# Ver_5_MAIN.net
KiCad netlist of a schematic drawn in EAGLE
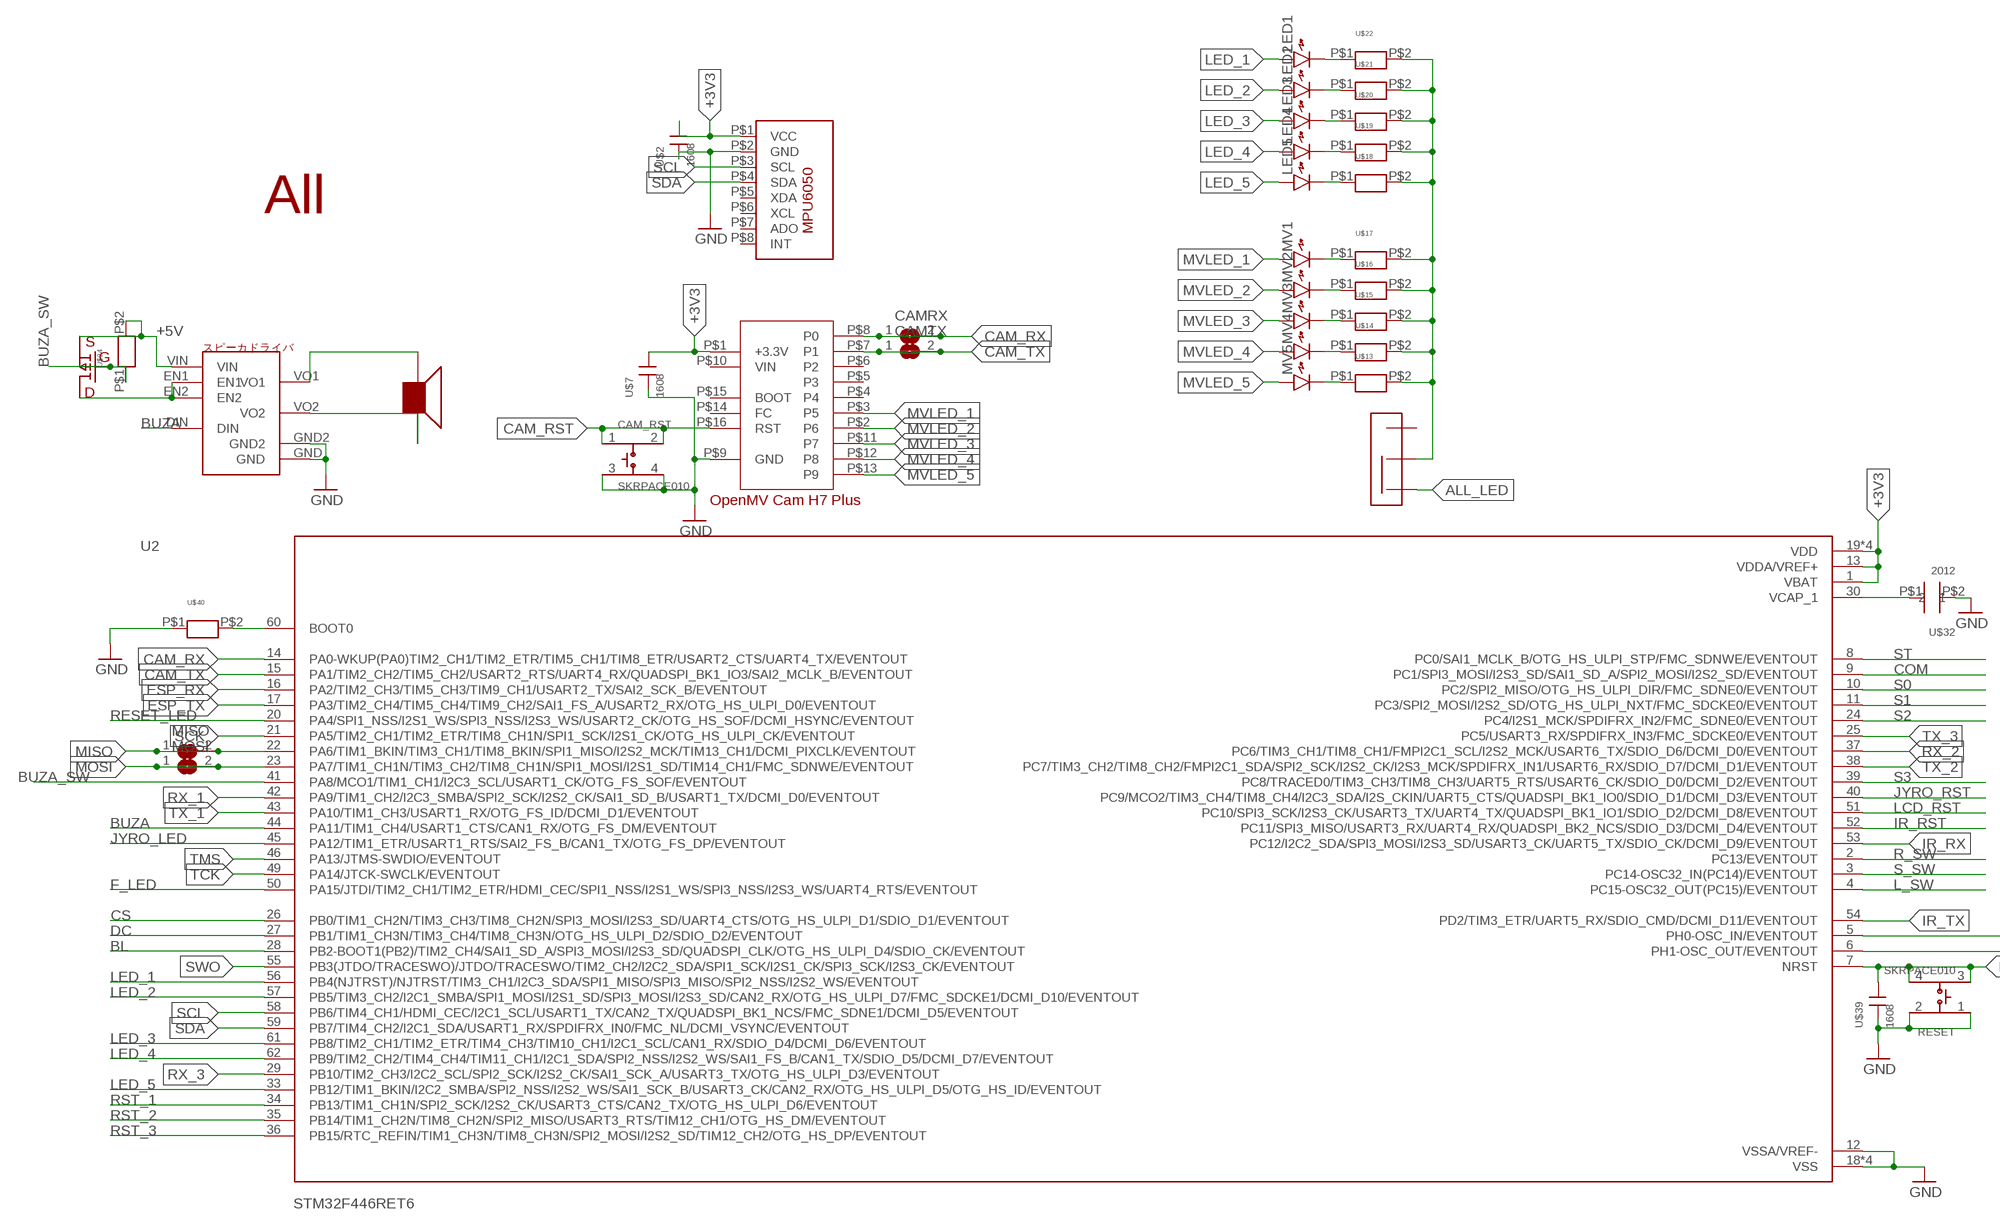
[diagram p0: schematic, sheet 1, part 1 of 2]
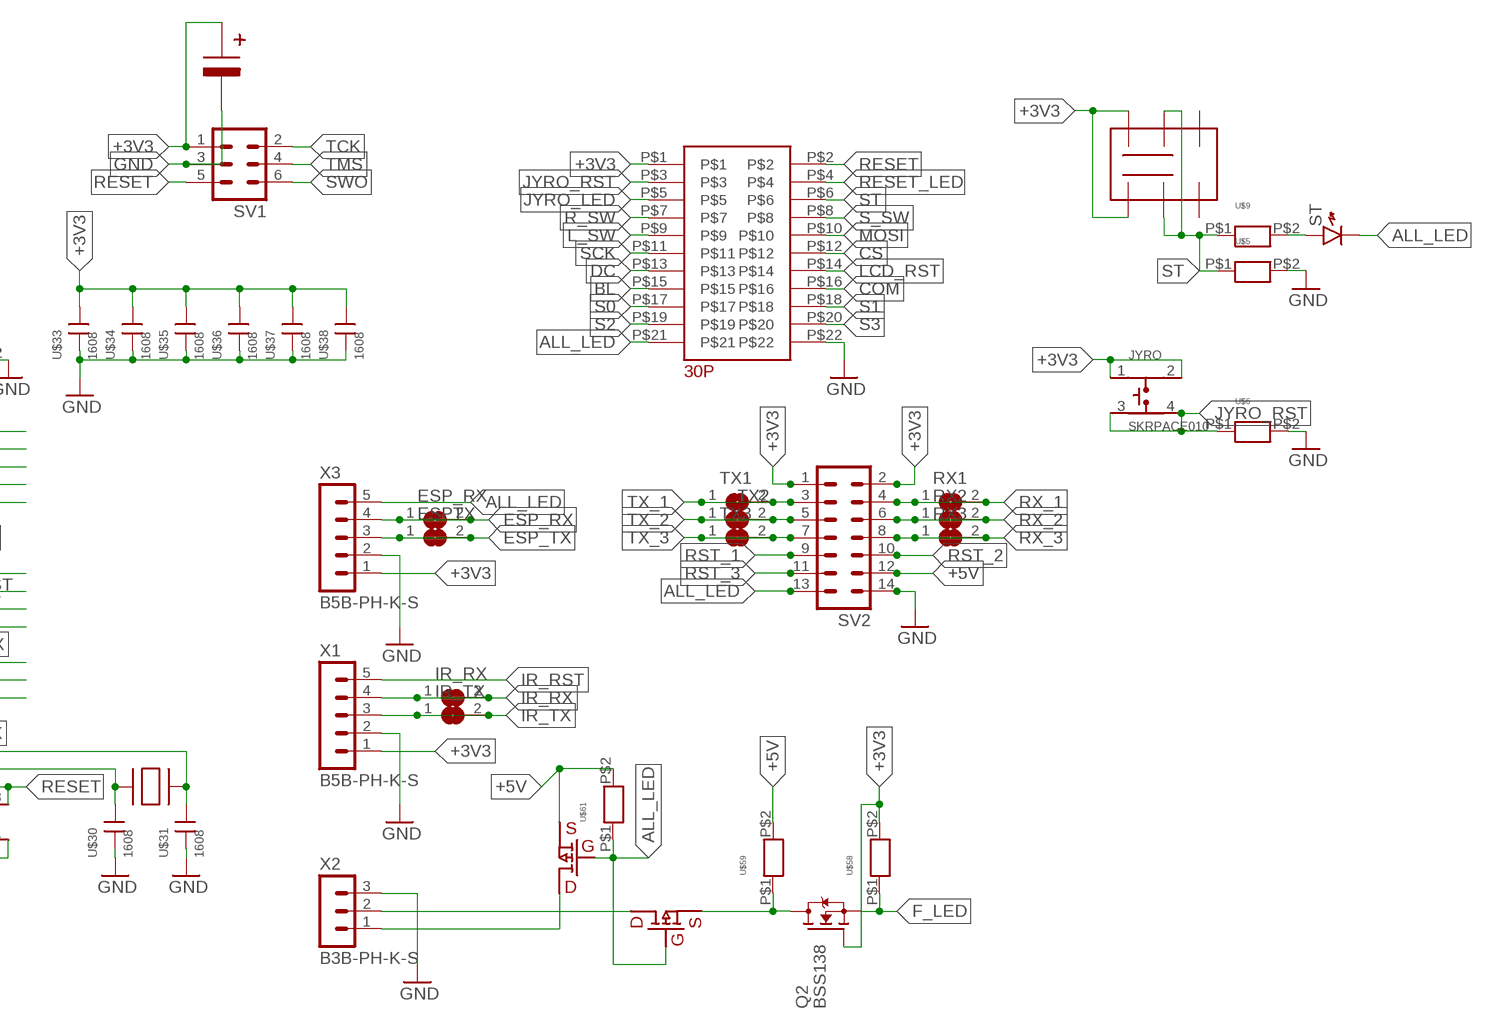
[diagram p1: schematic, sheet 1, part 2 of 2]

(export (version "E")
  (design (tool "Eeschema 10.0.6"))
  (components
    (comp (ref "CAMRX")
      (value "SJ")
      (footprint "eagle-import:SJ")
      (libsource (lib "eagle-import") (part "SJ"))
    )
    (comp (ref "CAMTX")
      (value "SJ")
      (footprint "eagle-import:SJ")
      (libsource (lib "eagle-import") (part "SJ"))
    )
    (comp (ref "CAM_RST")
      (value "SKRPACE010")
      (footprint "eagle-import:SW_SKRPACE010")
      (fields (field (name "MF") "ALPS"))
      (libsource (lib "eagle-import") (part "SKRPACE010"))
    )
    (comp (ref "ESPTX")
      (value "SJ")
      (footprint "eagle-import:SJ")
      (libsource (lib "eagle-import") (part "SJ"))
    )
    (comp (ref "ESP_RX")
      (value "SJ")
      (footprint "eagle-import:SJ")
      (libsource (lib "eagle-import") (part "SJ"))
    )
    (comp (ref "IR_RX")
      (value "SJ")
      (footprint "eagle-import:SJ")
      (libsource (lib "eagle-import") (part "SJ"))
    )
    (comp (ref "IR_TX")
      (value "SJ")
      (footprint "eagle-import:SJ")
      (libsource (lib "eagle-import") (part "SJ"))
    )
    (comp (ref "JYRO")
      (value "SKRPACE010")
      (footprint "eagle-import:SW_SKRPACE010")
      (fields (field (name "MF") "ALPS"))
      (libsource (lib "eagle-import") (part "SKRPACE010"))
    )
    (comp (ref "LED1")
      (value "LED1608")
      (footprint "eagle-import:LED1608")
      (libsource (lib "eagle-import") (part "LED1608"))
    )
    (comp (ref "LED2")
      (value "LED1608")
      (footprint "eagle-import:LED1608")
      (libsource (lib "eagle-import") (part "LED1608"))
    )
    (comp (ref "LED3")
      (value "LED1608")
      (footprint "eagle-import:LED1608")
      (libsource (lib "eagle-import") (part "LED1608"))
    )
    (comp (ref "LED4")
      (value "LED1608")
      (footprint "eagle-import:LED1608")
      (libsource (lib "eagle-import") (part "LED1608"))
    )
    (comp (ref "LED5")
      (value "LED1608")
      (footprint "eagle-import:LED1608")
      (libsource (lib "eagle-import") (part "LED1608"))
    )
    (comp (ref "MISO")
      (value "SJ")
      (footprint "eagle-import:SJ")
      (libsource (lib "eagle-import") (part "SJ"))
    )
    (comp (ref "MOSI")
      (value "SJ")
      (footprint "eagle-import:SJ")
      (libsource (lib "eagle-import") (part "SJ"))
    )
    (comp (ref "MV1")
      (value "LED1608")
      (footprint "eagle-import:LED1608")
      (libsource (lib "eagle-import") (part "LED1608"))
    )
    (comp (ref "MV2")
      (value "LED1608")
      (footprint "eagle-import:LED1608")
      (libsource (lib "eagle-import") (part "LED1608"))
    )
    (comp (ref "MV3")
      (value "LED1608")
      (footprint "eagle-import:LED1608")
      (libsource (lib "eagle-import") (part "LED1608"))
    )
    (comp (ref "MV4")
      (value "LED1608")
      (footprint "eagle-import:LED1608")
      (libsource (lib "eagle-import") (part "LED1608"))
    )
    (comp (ref "MV5")
      (value "LED1608")
      (footprint "eagle-import:LED1608")
      (libsource (lib "eagle-import") (part "LED1608"))
    )
    (comp (ref "Q2")
      (value "BSS138")
      (footprint "eagle-import:SOT23")
      (fields (field (name "MF") "Fairchild"))
      (libsource (lib "eagle-import") (part "BSS138"))
    )
    (comp (ref "RESET")
      (value "SKRPACE010")
      (footprint "eagle-import:SW_SKRPACE010")
      (fields (field (name "MF") "ALPS"))
      (libsource (lib "eagle-import") (part "SKRPACE010"))
    )
    (comp (ref "RX1") (value "SJ") (footprint "eagle-import:SJ") (libsource (lib "eagle-import") (part "SJ")))
    (comp (ref "RX2") (value "SJ") (footprint "eagle-import:SJ") (libsource (lib "eagle-import") (part "SJ")))
    (comp (ref "RX3") (value "SJ") (footprint "eagle-import:SJ") (libsource (lib "eagle-import") (part "SJ")))
    (comp (ref "ST")
      (value "LED1608")
      (footprint "eagle-import:LED1608")
      (libsource (lib "eagle-import") (part "LED1608"))
    )
    (comp (ref "SV1")
      (value "ML6L")
      (footprint "eagle-import:ML6L")
      (libsource (lib "eagle-import") (part "ML6L"))
    )
    (comp (ref "SV2")
      (value "ML14L")
      (footprint "eagle-import:ML14L")
      (libsource (lib "eagle-import") (part "ML14L"))
    )
    (comp (ref "TX1") (value "SJ") (footprint "eagle-import:SJ") (libsource (lib "eagle-import") (part "SJ")))
    (comp (ref "TX2") (value "SJ") (footprint "eagle-import:SJ") (libsource (lib "eagle-import") (part "SJ")))
    (comp (ref "TX3") (value "SJ") (footprint "eagle-import:SJ") (libsource (lib "eagle-import") (part "SJ")))
    (comp (ref "U$1")
      (value "OPENMV")
      (footprint "eagle-import:OPENMV")
      (libsource (lib "eagle-import") (part "OPENMV"))
    )
    (comp (ref "U$2")
      (value "1608")
      (footprint "eagle-import:CON")
      (libsource (lib "eagle-import") (part "1608"))
    )
    (comp (ref "U$3")
      (value "ジャイロ")
      (footprint "eagle-import:ジャイロ")
      (libsource (lib "eagle-import") (part "ジャイロ"))
    )
    (comp (ref "U$4")
      (value "LPRP")
      (footprint "eagle-import:LPRO")
      (libsource (lib "eagle-import") (part "LPRP"))
    )
    (comp (ref "U$5") (value "R") (footprint "eagle-import:1608") (libsource (lib "eagle-import") (part "R")))
    (comp (ref "U$6") (value "R") (footprint "eagle-import:1608") (libsource (lib "eagle-import") (part "R")))
    (comp (ref "U$7")
      (value "1608")
      (footprint "eagle-import:CON")
      (libsource (lib "eagle-import") (part "1608"))
    )
    (comp (ref "U$8")
      (value "22SW")
      (footprint "eagle-import:２２ｓｗ")
      (libsource (lib "eagle-import") (part "22SW"))
    )
    (comp (ref "U$9") (value "R") (footprint "eagle-import:1608") (libsource (lib "eagle-import") (part "R")))
    (comp (ref "U$10")
      (value "SSW")
      (footprint "eagle-import:SSW")
      (libsource (lib "eagle-import") (part "SSW"))
    )
    (comp (ref "U$11")
      (value "BUZA_DR")
      (footprint "eagle-import:BUZA_DR")
      (libsource (lib "eagle-import") (part "BUZA_DR"))
    )
    (comp (ref "U$12")
      (value "BUZA-")
      (footprint "eagle-import:ぶざー")
      (libsource (lib "eagle-import") (part "BUZA-"))
    )
    (comp (ref "U$13")
      (value "R")
      (footprint "eagle-import:1608")
      (libsource (lib "eagle-import") (part "R"))
    )
    (comp (ref "U$14")
      (value "R")
      (footprint "eagle-import:1608")
      (libsource (lib "eagle-import") (part "R"))
    )
    (comp (ref "U$15")
      (value "R")
      (footprint "eagle-import:1608")
      (libsource (lib "eagle-import") (part "R"))
    )
    (comp (ref "U$16")
      (value "R")
      (footprint "eagle-import:1608")
      (libsource (lib "eagle-import") (part "R"))
    )
    (comp (ref "U$17")
      (value "R")
      (footprint "eagle-import:1608")
      (libsource (lib "eagle-import") (part "R"))
    )
    (comp (ref "U$18")
      (value "R")
      (footprint "eagle-import:1608")
      (libsource (lib "eagle-import") (part "R"))
    )
    (comp (ref "U$19")
      (value "R")
      (footprint "eagle-import:1608")
      (libsource (lib "eagle-import") (part "R"))
    )
    (comp (ref "U$20")
      (value "R")
      (footprint "eagle-import:1608")
      (libsource (lib "eagle-import") (part "R"))
    )
    (comp (ref "U$21")
      (value "R")
      (footprint "eagle-import:1608")
      (libsource (lib "eagle-import") (part "R"))
    )
    (comp (ref "U$22")
      (value "R")
      (footprint "eagle-import:1608")
      (libsource (lib "eagle-import") (part "R"))
    )
    (comp (ref "U$23")
      (value "808")
      (footprint "eagle-import:808")
      (libsource (lib "eagle-import") (part "808"))
    )
    (comp (ref "U$24")
      (value "R")
      (footprint "eagle-import:1608")
      (libsource (lib "eagle-import") (part "R"))
    )
    (comp (ref "U$25")
      (value "10")
      (footprint "eagle-import:10")
      (libsource (lib "eagle-import") (part "10"))
    )
    (comp (ref "U$26")
      (value "ALL")
      (footprint "eagle-import:ALL")
      (libsource (lib "eagle-import") (part "ALL"))
    )
    (comp (ref "U$29")
      (value "SUISYOU")
      (footprint "eagle-import:水晶")
      (libsource (lib "eagle-import") (part "SUISYOU"))
    )
    (comp (ref "U$30")
      (value "1608")
      (footprint "eagle-import:CON")
      (libsource (lib "eagle-import") (part "1608"))
    )
    (comp (ref "U$31")
      (value "1608")
      (footprint "eagle-import:CON")
      (libsource (lib "eagle-import") (part "1608"))
    )
    (comp (ref "U$32")
      (value "2012")
      (footprint "eagle-import:2012")
      (libsource (lib "eagle-import") (part "2012"))
    )
    (comp (ref "U$33")
      (value "1608")
      (footprint "eagle-import:CON")
      (libsource (lib "eagle-import") (part "1608"))
    )
    (comp (ref "U$34")
      (value "1608")
      (footprint "eagle-import:CON")
      (libsource (lib "eagle-import") (part "1608"))
    )
    (comp (ref "U$35")
      (value "1608")
      (footprint "eagle-import:CON")
      (libsource (lib "eagle-import") (part "1608"))
    )
    (comp (ref "U$36")
      (value "1608")
      (footprint "eagle-import:CON")
      (libsource (lib "eagle-import") (part "1608"))
    )
    (comp (ref "U$37")
      (value "1608")
      (footprint "eagle-import:CON")
      (libsource (lib "eagle-import") (part "1608"))
    )
    (comp (ref "U$38")
      (value "1608")
      (footprint "eagle-import:CON")
      (libsource (lib "eagle-import") (part "1608"))
    )
    (comp (ref "U$39")
      (value "1608")
      (footprint "eagle-import:CON")
      (libsource (lib "eagle-import") (part "1608"))
    )
    (comp (ref "U$40")
      (value "R")
      (footprint "eagle-import:1608")
      (libsource (lib "eagle-import") (part "R"))
    )
    (comp (ref "U$58")
      (value "R")
      (footprint "eagle-import:1608")
      (libsource (lib "eagle-import") (part "R"))
    )
    (comp (ref "U$59")
      (value "R")
      (footprint "eagle-import:1608")
      (libsource (lib "eagle-import") (part "R"))
    )
    (comp (ref "U$60")
      (value "808")
      (footprint "eagle-import:808")
      (libsource (lib "eagle-import") (part "808"))
    )
    (comp (ref "U$61")
      (value "R")
      (footprint "eagle-import:1608")
      (libsource (lib "eagle-import") (part "R"))
    )
    (comp (ref "U$62")
      (value "808")
      (footprint "eagle-import:808")
      (libsource (lib "eagle-import") (part "808"))
    )
    (comp (ref "U2")
      (value "STM32F446RET6")
      (footprint "eagle-import:QFP50P1200X1200X160-64N")
      (fields (field (name "MF") "STMicroelectronics"))
      (libsource (lib "eagle-import") (part "STM32F446RET6"))
    )
    (comp (ref "X1")
      (value "B5B-PH-K-S")
      (footprint "eagle-import:B5B-PH-K-S")
      (libsource (lib "eagle-import") (part "B5B-PH-K-S"))
    )
    (comp (ref "X2")
      (value "B3B-PH-K-S")
      (footprint "eagle-import:B3B-PH-K-S")
      (libsource (lib "eagle-import") (part "B3B-PH-K-S"))
    )
    (comp (ref "X3")
      (value "B5B-PH-K-S")
      (footprint "eagle-import:B5B-PH-K-S")
      (libsource (lib "eagle-import") (part "B5B-PH-K-S"))
    )
  )
  (nets
    (net (code "1") (name "+3V3") (class "Default")
      (node (ref "JYRO") (pin "1") (pinfunction "1_1") (pintype "bidirectional"))
      (node (ref "JYRO") (pin "2") (pinfunction "2_2") (pintype "bidirectional"))
      (node (ref "Q2") (pin "1") (pinfunction "G_1") (pintype "passive"))
      (node (ref "SV1") (pin "1") (pinfunction "1_1") (pintype "passive"))
      (node (ref "SV2") (pin "1") (pinfunction "1_1") (pintype "passive"))
      (node (ref "SV2") (pin "2") (pinfunction "2_2") (pintype "passive"))
      (node (ref "U$1") (pin "P$1") (pinfunction "+3.3V_P$1") (pintype "bidirectional"))
      (node (ref "U$2") (pin "P$1") (pinfunction "1_P$1") (pintype "bidirectional"))
      (node (ref "U$25") (pin "P$1") (pinfunction "P$1_P$1") (pintype "bidirectional"))
      (node (ref "U$3") (pin "P$1") (pinfunction "VCC_P$1") (pintype "bidirectional"))
      (node (ref "U$33") (pin "P$1") (pinfunction "1_P$1") (pintype "bidirectional"))
      (node (ref "U$34") (pin "P$1") (pinfunction "1_P$1") (pintype "bidirectional"))
      (node (ref "U$35") (pin "P$1") (pinfunction "1_P$1") (pintype "bidirectional"))
      (node (ref "U$36") (pin "P$1") (pinfunction "1_P$1") (pintype "bidirectional"))
      (node (ref "U$37") (pin "P$1") (pinfunction "1_P$1") (pintype "bidirectional"))
      (node (ref "U$38") (pin "P$1") (pinfunction "1_P$1") (pintype "bidirectional"))
      (node (ref "U$4") (pin "P$1") (pinfunction "P$1_P$1") (pintype "bidirectional"))
      (node (ref "U$58") (pin "P$2") (pinfunction "P$2_P$2") (pintype "bidirectional"))
      (node (ref "U$7") (pin "P$1") (pinfunction "1_P$1") (pintype "bidirectional"))
      (node (ref "U$8") (pin "P$1") (pinfunction "P$1_P$1") (pintype "bidirectional"))
      (node (ref "U$8") (pin "P$4") (pinfunction "P$4_P$4") (pintype "bidirectional"))
      (node (ref "U2") (pin "1") (pinfunction "VBAT_1") (pintype "power_in"))
      (node (ref "U2") (pin "13") (pinfunction "VDDA/VREF+_13") (pintype "power_in"))
      (node (ref "U2") (pin "19") (pinfunction "VDD_19") (pintype "power_in"))
      (node (ref "U2") (pin "32") (pinfunction "VDD_32") (pintype "power_in"))
      (node (ref "U2") (pin "48") (pinfunction "VDD_48") (pintype "power_in"))
      (node (ref "U2") (pin "64") (pinfunction "VDD_64") (pintype "power_in"))
      (node (ref "X1") (pin "1") (pinfunction "1_1") (pintype "passive"))
      (node (ref "X3") (pin "1") (pinfunction "1_1") (pintype "passive"))
    )
    (net (code "2") (name "+5V") (class "Default")
      (node (ref "SV2") (pin "12") (pinfunction "12_12") (pintype "passive"))
      (node (ref "U$11") (pin "VIN") (pinfunction "VIN_VIN") (pintype "bidirectional"))
      (node (ref "U$23") (pin "S") (pinfunction "S_S") (pintype "bidirectional"))
      (node (ref "U$24") (pin "P$2") (pinfunction "P$2_P$2") (pintype "bidirectional"))
      (node (ref "U$59") (pin "P$2") (pinfunction "P$2_P$2") (pintype "bidirectional"))
      (node (ref "U$60") (pin "S") (pinfunction "S_S") (pintype "bidirectional"))
      (node (ref "U$61") (pin "P$2") (pinfunction "P$2_P$2") (pintype "bidirectional"))
    )
    (net (code "3") (name "/BUZA") (class "Default")
      (node (ref "U$11") (pin "DIN") (pinfunction "DIN_DIN") (pintype "bidirectional"))
      (node (ref "U2") (pin "44") (pinfunction "PA11/TIM1_CH4/USART1_CTS/CAN1_RX/OTG_FS_DM/EVENTOUT_44") (pintype "bidirectional"))
    )
    (net (code "4") (name "/BUZA_SW") (class "Default")
      (node (ref "U$23") (pin "G") (pinfunction "G_G") (pintype "bidirectional"))
      (node (ref "U$24") (pin "P$1") (pinfunction "P$1_P$1") (pintype "bidirectional"))
      (node (ref "U2") (pin "41") (pinfunction "PA8/MCO1/TIM1_CH1/I2C3_SCL/USART1_CK/OTG_FS_SOF/EVENTOUT_41") (pintype "bidirectional"))
    )
    (net (code "5") (name "ALL_LED") (class "Default")
      (node (ref "ST") (pin "K") (pinfunction "K_K") (pintype "passive"))
      (node (ref "SV2") (pin "13") (pinfunction "13_13") (pintype "passive"))
      (node (ref "U$10") (pin "P$1") (pinfunction "P$1_P$1") (pintype "bidirectional"))
      (node (ref "U$4") (pin "P$21") (pinfunction "P$21_P$21") (pintype "bidirectional"))
      (node (ref "U$60") (pin "G") (pinfunction "G_G") (pintype "bidirectional"))
      (node (ref "U$61") (pin "P$1") (pinfunction "P$1_P$1") (pintype "bidirectional"))
      (node (ref "U$62") (pin "G") (pinfunction "G_G") (pintype "bidirectional"))
      (node (ref "X3") (pin "5") (pinfunction "5_5") (pintype "passive"))
    )
    (net (code "6") (name "BL") (class "Default")
      (node (ref "U$4") (pin "P$15") (pinfunction "P$15_P$15") (pintype "bidirectional"))
      (node (ref "U2") (pin "28") (pinfunction "PB2-BOOT1(PB2)/TIM2_CH4/SAI1_SD_A/SPI3_MOSI/I2S3_SD/QUADSPI_CLK/OTG_HS_ULPI_D4/SDIO_CK/EVENTOUT_28") (pintype "bidirectional"))
    )
    (net (code "7") (name "CAM_RST") (class "Default")
      (node (ref "CAM_RST") (pin "1") (pinfunction "1_1") (pintype "bidirectional"))
      (node (ref "CAM_RST") (pin "2") (pinfunction "2_2") (pintype "bidirectional"))
      (node (ref "U$1") (pin "P$16") (pinfunction "RST_P$16") (pintype "bidirectional"))
    )
    (net (code "8") (name "CAM_RX") (class "Default")
      (node (ref "CAMRX") (pin "1") (pinfunction "1_1") (pintype "passive"))
      (node (ref "CAMRX") (pin "2") (pinfunction "2_2") (pintype "passive"))
      (node (ref "U$1") (pin "P$8") (pinfunction "P0_P$8") (pintype "bidirectional"))
      (node (ref "U2") (pin "14") (pinfunction "PA0-WKUP(PA0)TIM2_CH1/TIM2_ETR/TIM5_CH1/TIM8_ETR/USART2_CTS/UART4_TX/EVENTOUT_14") (pintype "bidirectional"))
    )
    (net (code "9") (name "CAM_TX") (class "Default")
      (node (ref "CAMTX") (pin "1") (pinfunction "1_1") (pintype "passive"))
      (node (ref "CAMTX") (pin "2") (pinfunction "2_2") (pintype "passive"))
      (node (ref "U$1") (pin "P$7") (pinfunction "P1_P$7") (pintype "bidirectional"))
      (node (ref "U2") (pin "15") (pinfunction "PA1/TIM2_CH2/TIM5_CH2/USART2_RTS/UART4_RX/QUADSPI_BK1_IO3/SAI2_MCLK_B/EVENTOUT_15") (pintype "bidirectional"))
    )
    (net (code "10") (name "COM") (class "Default")
      (node (ref "U$4") (pin "P$16") (pinfunction "P$16_P$16") (pintype "bidirectional"))
      (node (ref "U2") (pin "9") (pinfunction "PC1/SPI3_MOSI/I2S3_SD/SAI1_SD_A/SPI2_MOSI/I2S2_SD/EVENTOUT_9") (pintype "bidirectional"))
    )
    (net (code "11") (name "CS") (class "Default")
      (node (ref "U$4") (pin "P$12") (pinfunction "P$12_P$12") (pintype "bidirectional"))
      (node (ref "U2") (pin "26") (pinfunction "PB0/TIM1_CH2N/TIM3_CH3/TIM8_CH2N/SPI3_MOSI/I2S3_SD/UART4_CTS/OTG_HS_ULPI_D1/SDIO_D1/EVENTOUT_26") (pintype "bidirectional"))
    )
    (net (code "12") (name "DC") (class "Default")
      (node (ref "U$4") (pin "P$13") (pinfunction "P$13_P$13") (pintype "bidirectional"))
      (node (ref "U2") (pin "27") (pinfunction "PB1/TIM1_CH3N/TIM3_CH4/TIM8_CH3N/OTG_HS_ULPI_D2/SDIO_D2/EVENTOUT_27") (pintype "bidirectional"))
    )
    (net (code "13") (name "ESP_RX") (class "Default")
      (node (ref "ESP_RX") (pin "1") (pinfunction "1_1") (pintype "passive"))
      (node (ref "ESP_RX") (pin "2") (pinfunction "2_2") (pintype "passive"))
      (node (ref "U2") (pin "16") (pinfunction "PA2/TIM2_CH3/TIM5_CH3/TIM9_CH1/USART2_TX/SAI2_SCK_B/EVENTOUT_16") (pintype "bidirectional"))
      (node (ref "X3") (pin "4") (pinfunction "4_4") (pintype "passive"))
    )
    (net (code "14") (name "ESP_TX") (class "Default")
      (node (ref "ESPTX") (pin "1") (pinfunction "1_1") (pintype "passive"))
      (node (ref "ESPTX") (pin "2") (pinfunction "2_2") (pintype "passive"))
      (node (ref "U2") (pin "17") (pinfunction "PA3/TIM2_CH4/TIM5_CH4/TIM9_CH2/SAI1_FS_A/USART2_RX/OTG_HS_ULPI_D0/EVENTOUT_17") (pintype "bidirectional"))
      (node (ref "X3") (pin "3") (pinfunction "3_3") (pintype "passive"))
    )
    (net (code "15") (name "F_LED") (class "Default")
      (node (ref "Q2") (pin "2") (pinfunction "S_2") (pintype "passive"))
      (node (ref "U$58") (pin "P$1") (pinfunction "P$1_P$1") (pintype "bidirectional"))
      (node (ref "U2") (pin "50") (pinfunction "PA15/JTDI/TIM2_CH1/TIM2_ETR/HDMI_CEC/SPI1_NSS/I2S1_WS/SPI3_NSS/I2S3_WS/UART4_RTS/EVENTOUT_50") (pintype "bidirectional"))
    )
    (net (code "16") (name "GND") (class "Default")
      (node (ref "CAM_RST") (pin "3") (pinfunction "3_3") (pintype "bidirectional"))
      (node (ref "CAM_RST") (pin "4") (pinfunction "4_4") (pintype "bidirectional"))
      (node (ref "RESET") (pin "1") (pinfunction "1_1") (pintype "bidirectional"))
      (node (ref "RESET") (pin "2") (pinfunction "2_2") (pintype "bidirectional"))
      (node (ref "SV1") (pin "3") (pinfunction "3_3") (pintype "passive"))
      (node (ref "SV2") (pin "14") (pinfunction "14_14") (pintype "passive"))
      (node (ref "U$1") (pin "P$9") (pinfunction "GND_P$9") (pintype "bidirectional"))
      (node (ref "U$11") (pin "GND") (pinfunction "GND_GND") (pintype "bidirectional"))
      (node (ref "U$11") (pin "GND2") (pinfunction "GND2_GND2") (pintype "bidirectional"))
      (node (ref "U$2") (pin "P$2") (pinfunction "2_P$2") (pintype "bidirectional"))
      (node (ref "U$25") (pin "P$2") (pinfunction "P$2_P$2") (pintype "bidirectional"))
      (node (ref "U$3") (pin "P$2") (pinfunction "GND_P$2") (pintype "bidirectional"))
      (node (ref "U$30") (pin "P$2") (pinfunction "2_P$2") (pintype "bidirectional"))
      (node (ref "U$31") (pin "P$2") (pinfunction "2_P$2") (pintype "bidirectional"))
      (node (ref "U$32") (pin "P$2") (pinfunction "2_P$2") (pintype "bidirectional"))
      (node (ref "U$33") (pin "P$2") (pinfunction "2_P$2") (pintype "bidirectional"))
      (node (ref "U$34") (pin "P$2") (pinfunction "2_P$2") (pintype "bidirectional"))
      (node (ref "U$35") (pin "P$2") (pinfunction "2_P$2") (pintype "bidirectional"))
      (node (ref "U$36") (pin "P$2") (pinfunction "2_P$2") (pintype "bidirectional"))
      (node (ref "U$37") (pin "P$2") (pinfunction "2_P$2") (pintype "bidirectional"))
      (node (ref "U$38") (pin "P$2") (pinfunction "2_P$2") (pintype "bidirectional"))
      (node (ref "U$39") (pin "P$2") (pinfunction "2_P$2") (pintype "bidirectional"))
      (node (ref "U$4") (pin "P$22") (pinfunction "P$22_P$22") (pintype "bidirectional"))
      (node (ref "U$40") (pin "P$1") (pinfunction "P$1_P$1") (pintype "bidirectional"))
      (node (ref "U$5") (pin "P$2") (pinfunction "P$2_P$2") (pintype "bidirectional"))
      (node (ref "U$6") (pin "P$2") (pinfunction "P$2_P$2") (pintype "bidirectional"))
      (node (ref "U$7") (pin "P$2") (pinfunction "2_P$2") (pintype "bidirectional"))
      (node (ref "U2") (pin "12") (pinfunction "VSSA/VREF-_12") (pintype "power_in"))
      (node (ref "U2") (pin "18") (pinfunction "VSS_18") (pintype "power_in"))
      (node (ref "U2") (pin "31") (pinfunction "VSS_31") (pintype "power_in"))
      (node (ref "U2") (pin "47") (pinfunction "VSS_47") (pintype "power_in"))
      (node (ref "U2") (pin "63") (pinfunction "VSS_63") (pintype "power_in"))
      (node (ref "X1") (pin "2") (pinfunction "2_2") (pintype "passive"))
      (node (ref "X2") (pin "3") (pinfunction "3_3") (pintype "passive"))
      (node (ref "X3") (pin "2") (pinfunction "2_2") (pintype "passive"))
    )
    (net (code "17") (name "IR_RST") (class "Default")
      (node (ref "U2") (pin "52") (pinfunction "PC11/SPI3_MISO/USART3_RX/UART4_RX/QUADSPI_BK2_NCS/SDIO_D3/DCMI_D4/EVENTOUT_52") (pintype "bidirectional"))
      (node (ref "X1") (pin "5") (pinfunction "5_5") (pintype "passive"))
    )
    (net (code "18") (name "IR_RX") (class "Default")
      (node (ref "IR_RX") (pin "1") (pinfunction "1_1") (pintype "passive"))
      (node (ref "IR_RX") (pin "2") (pinfunction "2_2") (pintype "passive"))
      (node (ref "U2") (pin "53") (pinfunction "PC12/I2C2_SDA/SPI3_MOSI/I2S3_SD/USART3_CK/UART5_TX/SDIO_CK/DCMI_D9/EVENTOUT_53") (pintype "bidirectional"))
      (node (ref "X1") (pin "4") (pinfunction "4_4") (pintype "passive"))
    )
    (net (code "19") (name "IR_TX") (class "Default")
      (node (ref "IR_TX") (pin "1") (pinfunction "1_1") (pintype "passive"))
      (node (ref "IR_TX") (pin "2") (pinfunction "2_2") (pintype "passive"))
      (node (ref "U2") (pin "54") (pinfunction "PD2/TIM3_ETR/UART5_RX/SDIO_CMD/DCMI_D11/EVENTOUT_54") (pintype "bidirectional"))
      (node (ref "X1") (pin "3") (pinfunction "3_3") (pintype "passive"))
    )
    (net (code "20") (name "JYRO_LED") (class "Default")
      (node (ref "U$4") (pin "P$5") (pinfunction "P$5_P$5") (pintype "bidirectional"))
      (node (ref "U2") (pin "45") (pinfunction "PA12/TIM1_ETR/USART1_RTS/SAI2_FS_B/CAN1_TX/OTG_FS_DP/EVENTOUT_45") (pintype "bidirectional"))
    )
    (net (code "21") (name "JYRO_RST") (class "Default")
      (node (ref "JYRO") (pin "3") (pinfunction "3_3") (pintype "bidirectional"))
      (node (ref "JYRO") (pin "4") (pinfunction "4_4") (pintype "bidirectional"))
      (node (ref "U$4") (pin "P$3") (pinfunction "P$3_P$3") (pintype "bidirectional"))
      (node (ref "U$6") (pin "P$1") (pinfunction "P$1_P$1") (pintype "bidirectional"))
      (node (ref "U2") (pin "40") (pinfunction "PC9/MCO2/TIM3_CH4/TIM8_CH4/I2C3_SDA/I2S_CKIN/UART5_CTS/QUADSPI_BK1_IO0/SDIO_D1/DCMI_D3/EVENTOUT_40") (pintype "bidirectional"))
    )
    (net (code "22") (name "LCD_RST") (class "Default")
      (node (ref "U$4") (pin "P$14") (pinfunction "P$14_P$14") (pintype "bidirectional"))
      (node (ref "U2") (pin "51") (pinfunction "PC10/SPI3_SCK/I2S3_CK/USART3_TX/UART4_TX/QUADSPI_BK1_IO1/SDIO_D2/DCMI_D8/EVENTOUT_51") (pintype "bidirectional"))
    )
    (net (code "23") (name "LED_1") (class "Default")
      (node (ref "LED1") (pin "A") (pinfunction "A_A") (pintype "passive"))
      (node (ref "U2") (pin "56") (pinfunction "PB4(NJTRST)/NJTRST/TIM3_CH1/I2C3_SDA/SPI1_MISO/SPI3_MISO/SPI2_NSS/I2S2_WS/EVENTOUT_56") (pintype "bidirectional"))
    )
    (net (code "24") (name "LED_2") (class "Default")
      (node (ref "LED2") (pin "A") (pinfunction "A_A") (pintype "passive"))
      (node (ref "U2") (pin "57") (pinfunction "PB5/TIM3_CH2/I2C1_SMBA/SPI1_MOSI/I2S1_SD/SPI3_MOSI/I2S3_SD/CAN2_RX/OTG_HS_ULPI_D7/FMC_SDCKE1/DCMI_D10/EVENTOUT_57") (pintype "bidirectional"))
    )
    (net (code "25") (name "LED_3") (class "Default")
      (node (ref "LED3") (pin "A") (pinfunction "A_A") (pintype "passive"))
      (node (ref "U2") (pin "61") (pinfunction "PB8/TIM2_CH1/TIM2_ETR/TIM4_CH3/TIM10_CH1/I2C1_SCL/CAN1_RX/SDIO_D4/DCMI_D6/EVENTOUT_61") (pintype "bidirectional"))
    )
    (net (code "26") (name "LED_4") (class "Default")
      (node (ref "LED4") (pin "A") (pinfunction "A_A") (pintype "passive"))
      (node (ref "U2") (pin "62") (pinfunction "PB9/TIM2_CH2/TIM4_CH4/TIM11_CH1/I2C1_SDA/SPI2_NSS/I2S2_WS/SAI1_FS_B/CAN1_TX/SDIO_D5/DCMI_D7/EVENTOUT_62") (pintype "bidirectional"))
    )
    (net (code "27") (name "LED_5") (class "Default")
      (node (ref "LED5") (pin "A") (pinfunction "A_A") (pintype "passive"))
      (node (ref "U2") (pin "33") (pinfunction "PB12/TIM1_BKIN/I2C2_SMBA/SPI2_NSS/I2S2_WS/SAI1_SCK_B/USART3_CK/CAN2_RX/OTG_HS_ULPI_D5/OTG_HS_ID/EVENTOUT_33") (pintype "bidirectional"))
    )
    (net (code "28") (name "L_SW") (class "Default")
      (node (ref "U$4") (pin "P$9") (pinfunction "P$9_P$9") (pintype "bidirectional"))
      (node (ref "U2") (pin "4") (pinfunction "PC15-OSC32_OUT(PC15)/EVENTOUT_4") (pintype "bidirectional"))
    )
    (net (code "29") (name "MISO") (class "Default")
      (node (ref "MISO") (pin "1") (pinfunction "1_1") (pintype "passive"))
      (node (ref "MISO") (pin "2") (pinfunction "2_2") (pintype "passive"))
      (node (ref "U2") (pin "22") (pinfunction "PA6/TIM1_BKIN/TIM3_CH1/TIM8_BKIN/SPI1_MISO/I2S2_MCK/TIM13_CH1/DCMI_PIXCLK/EVENTOUT_22") (pintype "bidirectional"))
    )
    (net (code "30") (name "MOSI") (class "Default")
      (node (ref "MOSI") (pin "1") (pinfunction "1_1") (pintype "passive"))
      (node (ref "MOSI") (pin "2") (pinfunction "2_2") (pintype "passive"))
      (node (ref "U$4") (pin "P$10") (pinfunction "P$10_P$10") (pintype "bidirectional"))
      (node (ref "U2") (pin "23") (pinfunction "PA7/TIM1_CH1N/TIM3_CH2/TIM8_CH1N/SPI1_MOSI/I2S1_SD/TIM14_CH1/FMC_SDNWE/EVENTOUT_23") (pintype "bidirectional"))
    )
    (net (code "31") (name "MVLED_1") (class "Default")
      (node (ref "MV1") (pin "A") (pinfunction "A_A") (pintype "passive"))
      (node (ref "U$1") (pin "P$3") (pinfunction "P5_P$3") (pintype "bidirectional"))
    )
    (net (code "32") (name "MVLED_2") (class "Default")
      (node (ref "MV2") (pin "A") (pinfunction "A_A") (pintype "passive"))
      (node (ref "U$1") (pin "P$2") (pinfunction "P6_P$2") (pintype "bidirectional"))
    )
    (net (code "33") (name "MVLED_3") (class "Default")
      (node (ref "MV3") (pin "A") (pinfunction "A_A") (pintype "passive"))
      (node (ref "U$1") (pin "P$11") (pinfunction "P7_P$11") (pintype "bidirectional"))
    )
    (net (code "34") (name "MVLED_4") (class "Default")
      (node (ref "MV4") (pin "A") (pinfunction "A_A") (pintype "passive"))
      (node (ref "U$1") (pin "P$12") (pinfunction "P8_P$12") (pintype "bidirectional"))
    )
    (net (code "35") (name "MVLED_5") (class "Default")
      (node (ref "MV5") (pin "A") (pinfunction "A_A") (pintype "passive"))
      (node (ref "U$1") (pin "P$13") (pinfunction "P9_P$13") (pintype "bidirectional"))
    )
    (net (code "36") (name "Net-(LED1-PadK)") (class "Default")
      (node (ref "LED1") (pin "K") (pinfunction "K_K") (pintype "passive"))
      (node (ref "U$22") (pin "P$1") (pinfunction "P$1_P$1") (pintype "bidirectional"))
    )
    (net (code "37") (name "Net-(LED2-PadK)") (class "Default")
      (node (ref "LED2") (pin "K") (pinfunction "K_K") (pintype "passive"))
      (node (ref "U$21") (pin "P$1") (pinfunction "P$1_P$1") (pintype "bidirectional"))
    )
    (net (code "38") (name "Net-(LED3-PadK)") (class "Default")
      (node (ref "LED3") (pin "K") (pinfunction "K_K") (pintype "passive"))
      (node (ref "U$20") (pin "P$1") (pinfunction "P$1_P$1") (pintype "bidirectional"))
    )
    (net (code "39") (name "Net-(LED4-PadK)") (class "Default")
      (node (ref "LED4") (pin "K") (pinfunction "K_K") (pintype "passive"))
      (node (ref "U$19") (pin "P$1") (pinfunction "P$1_P$1") (pintype "bidirectional"))
    )
    (net (code "40") (name "Net-(LED5-PadK)") (class "Default")
      (node (ref "LED5") (pin "K") (pinfunction "K_K") (pintype "passive"))
      (node (ref "U$18") (pin "P$1") (pinfunction "P$1_P$1") (pintype "bidirectional"))
    )
    (net (code "41") (name "Net-(MV1-PadK)") (class "Default")
      (node (ref "MV1") (pin "K") (pinfunction "K_K") (pintype "passive"))
      (node (ref "U$17") (pin "P$1") (pinfunction "P$1_P$1") (pintype "bidirectional"))
    )
    (net (code "42") (name "Net-(MV2-PadK)") (class "Default")
      (node (ref "MV2") (pin "K") (pinfunction "K_K") (pintype "passive"))
      (node (ref "U$16") (pin "P$1") (pinfunction "P$1_P$1") (pintype "bidirectional"))
    )
    (net (code "43") (name "Net-(MV3-PadK)") (class "Default")
      (node (ref "MV3") (pin "K") (pinfunction "K_K") (pintype "passive"))
      (node (ref "U$15") (pin "P$1") (pinfunction "P$1_P$1") (pintype "bidirectional"))
    )
    (net (code "44") (name "Net-(MV4-PadK)") (class "Default")
      (node (ref "MV4") (pin "K") (pinfunction "K_K") (pintype "passive"))
      (node (ref "U$14") (pin "P$1") (pinfunction "P$1_P$1") (pintype "bidirectional"))
    )
    (net (code "45") (name "Net-(MV5-PadK)") (class "Default")
      (node (ref "MV5") (pin "K") (pinfunction "K_K") (pintype "passive"))
      (node (ref "U$13") (pin "P$1") (pinfunction "P$1_P$1") (pintype "bidirectional"))
    )
    (net (code "46") (name "Net-(Q2-D)") (class "Default")
      (node (ref "Q2") (pin "3") (pinfunction "D_3") (pintype "passive"))
      (node (ref "U$59") (pin "P$1") (pinfunction "P$1_P$1") (pintype "bidirectional"))
      (node (ref "U$62") (pin "S") (pinfunction "S_S") (pintype "bidirectional"))
    )
    (net (code "47") (name "Net-(ST-PadA)") (class "Default")
      (node (ref "ST") (pin "A") (pinfunction "A_A") (pintype "passive"))
      (node (ref "U$9") (pin "P$2") (pinfunction "P$2_P$2") (pintype "bidirectional"))
    )
    (net (code "48") (name "Net-(U$10-P$2)") (class "Default")
      (node (ref "U$10") (pin "P$3") (pinfunction "P$2_P$3") (pintype "bidirectional"))
      (node (ref "U$13") (pin "P$2") (pinfunction "P$2_P$2") (pintype "bidirectional"))
      (node (ref "U$14") (pin "P$2") (pinfunction "P$2_P$2") (pintype "bidirectional"))
      (node (ref "U$15") (pin "P$2") (pinfunction "P$2_P$2") (pintype "bidirectional"))
      (node (ref "U$16") (pin "P$2") (pinfunction "P$2_P$2") (pintype "bidirectional"))
      (node (ref "U$17") (pin "P$2") (pinfunction "P$2_P$2") (pintype "bidirectional"))
      (node (ref "U$18") (pin "P$2") (pinfunction "P$2_P$2") (pintype "bidirectional"))
      (node (ref "U$19") (pin "P$2") (pinfunction "P$2_P$2") (pintype "bidirectional"))
      (node (ref "U$20") (pin "P$2") (pinfunction "P$2_P$2") (pintype "bidirectional"))
      (node (ref "U$21") (pin "P$2") (pinfunction "P$2_P$2") (pintype "bidirectional"))
      (node (ref "U$22") (pin "P$2") (pinfunction "P$2_P$2") (pintype "bidirectional"))
    )
    (net (code "49") (name "Net-(U$11-PadEN1)") (class "Default")
      (node (ref "U$11") (pin "EN1") (pinfunction "EN1_EN1") (pintype "bidirectional"))
      (node (ref "U$11") (pin "EN2") (pinfunction "EN2_EN2") (pintype "bidirectional"))
      (node (ref "U$23") (pin "D") (pinfunction "D_D") (pintype "bidirectional"))
      (node (ref "U$23") (pin "DD") (pinfunction "D_DD") (pintype "bidirectional"))
      (node (ref "U$23") (pin "DDD") (pinfunction "D_DDD") (pintype "bidirectional"))
      (node (ref "U$23") (pin "DDDD") (pinfunction "D_DDDD") (pintype "bidirectional"))
    )
    (net (code "50") (name "Net-(U$11-PadVO1)") (class "Default")
      (node (ref "U$11") (pin "VO1") (pinfunction "VO1_VO1") (pintype "bidirectional"))
      (node (ref "U$12") (pin "P$1") (pinfunction "P$1_P$1") (pintype "bidirectional"))
    )
    (net (code "51") (name "Net-(U$11-PadVO2)") (class "Default")
      (node (ref "U$11") (pin "VO2") (pinfunction "VO2_VO2") (pintype "bidirectional"))
      (node (ref "U$12") (pin "P$2") (pinfunction "P$2_P$2") (pintype "bidirectional"))
    )
    (net (code "52") (name "Net-(U$30-1)") (class "Default")
      (node (ref "U$29") (pin "P$1") (pinfunction "P$1_P$1") (pintype "bidirectional"))
      (node (ref "U$30") (pin "P$1") (pinfunction "1_P$1") (pintype "bidirectional"))
      (node (ref "U2") (pin "6") (pinfunction "PH1-OSC_OUT/EVENTOUT_6") (pintype "bidirectional"))
    )
    (net (code "53") (name "Net-(U$31-1)") (class "Default")
      (node (ref "U$29") (pin "P$2") (pinfunction "P$2_P$2") (pintype "bidirectional"))
      (node (ref "U$31") (pin "P$1") (pinfunction "1_P$1") (pintype "bidirectional"))
      (node (ref "U2") (pin "5") (pinfunction "PH0-OSC_IN/EVENTOUT_5") (pintype "bidirectional"))
    )
    (net (code "54") (name "Net-(U$32-1)") (class "Default")
      (node (ref "U$32") (pin "P$1") (pinfunction "1_P$1") (pintype "bidirectional"))
      (node (ref "U2") (pin "30") (pinfunction "VCAP_1_30") (pintype "power_in"))
    )
    (net (code "55") (name "Net-(U$60-D-PadDD)") (class "Default")
      (node (ref "U$60") (pin "D") (pinfunction "D_D") (pintype "bidirectional"))
      (node (ref "U$60") (pin "DD") (pinfunction "D_DD") (pintype "bidirectional"))
      (node (ref "U$60") (pin "DDD") (pinfunction "D_DDD") (pintype "bidirectional"))
      (node (ref "U$60") (pin "DDDD") (pinfunction "D_DDDD") (pintype "bidirectional"))
      (node (ref "X2") (pin "1") (pinfunction "1_1") (pintype "passive"))
    )
    (net (code "56") (name "Net-(U$62-D-PadDD)") (class "Default")
      (node (ref "U$62") (pin "D") (pinfunction "D_D") (pintype "bidirectional"))
      (node (ref "U$62") (pin "DD") (pinfunction "D_DD") (pintype "bidirectional"))
      (node (ref "U$62") (pin "DDD") (pinfunction "D_DDD") (pintype "bidirectional"))
      (node (ref "U$62") (pin "DDDD") (pinfunction "D_DDDD") (pintype "bidirectional"))
      (node (ref "X2") (pin "2") (pinfunction "2_2") (pintype "passive"))
    )
    (net (code "57") (name "Net-(U2-BOOT0)") (class "Default")
      (node (ref "U$40") (pin "P$2") (pinfunction "P$2_P$2") (pintype "bidirectional"))
      (node (ref "U2") (pin "60") (pinfunction "BOOT0_60") (pintype "input"))
    )
    (net (code "58") (name "RESET") (class "Default")
      (node (ref "RESET") (pin "3") (pinfunction "3_3") (pintype "bidirectional"))
      (node (ref "RESET") (pin "4") (pinfunction "4_4") (pintype "bidirectional"))
      (node (ref "SV1") (pin "5") (pinfunction "5_5") (pintype "passive"))
      (node (ref "U$39") (pin "P$1") (pinfunction "1_P$1") (pintype "bidirectional"))
      (node (ref "U$4") (pin "P$2") (pinfunction "P$2_P$2") (pintype "bidirectional"))
      (node (ref "U2") (pin "7") (pinfunction "NRST_7") (pintype "bidirectional"))
    )
    (net (code "59") (name "RESET_LED") (class "Default")
      (node (ref "U$4") (pin "P$4") (pinfunction "P$4_P$4") (pintype "bidirectional"))
      (node (ref "U2") (pin "20") (pinfunction "PA4/SPI1_NSS/I2S1_WS/SPI3_NSS/I2S3_WS/USART2_CK/OTG_HS_SOF/DCMI_HSYNC/EVENTOUT_20") (pintype "bidirectional"))
    )
    (net (code "60") (name "RST_1") (class "Default")
      (node (ref "SV2") (pin "9") (pinfunction "9_9") (pintype "passive"))
      (node (ref "U2") (pin "34") (pinfunction "PB13/TIM1_CH1N/SPI2_SCK/I2S2_CK/USART3_CTS/CAN2_TX/OTG_HS_ULPI_D6/EVENTOUT_34") (pintype "bidirectional"))
    )
    (net (code "61") (name "RST_2") (class "Default")
      (node (ref "SV2") (pin "10") (pinfunction "10_10") (pintype "passive"))
      (node (ref "U2") (pin "35") (pinfunction "PB14/TIM1_CH2N/TIM8_CH2N/SPI2_MISO/USART3_RTS/TIM12_CH1/OTG_HS_DM/EVENTOUT_35") (pintype "bidirectional"))
    )
    (net (code "62") (name "RST_3") (class "Default")
      (node (ref "SV2") (pin "11") (pinfunction "11_11") (pintype "passive"))
      (node (ref "U2") (pin "36") (pinfunction "PB15/RTC_REFIN/TIM1_CH3N/TIM8_CH3N/SPI2_MOSI/I2S2_SD/TIM12_CH2/OTG_HS_DP/EVENTOUT_36") (pintype "bidirectional"))
    )
    (net (code "63") (name "RX_1") (class "Default")
      (node (ref "RX1") (pin "1") (pinfunction "1_1") (pintype "passive"))
      (node (ref "RX1") (pin "2") (pinfunction "2_2") (pintype "passive"))
      (node (ref "SV2") (pin "4") (pinfunction "4_4") (pintype "passive"))
      (node (ref "U2") (pin "42") (pinfunction "PA9/TIM1_CH2/I2C3_SMBA/SPI2_SCK/I2S2_CK/SAI1_SD_B/USART1_TX/DCMI_D0/EVENTOUT_42") (pintype "bidirectional"))
    )
    (net (code "64") (name "RX_2") (class "Default")
      (node (ref "RX2") (pin "1") (pinfunction "1_1") (pintype "passive"))
      (node (ref "RX2") (pin "2") (pinfunction "2_2") (pintype "passive"))
      (node (ref "SV2") (pin "6") (pinfunction "6_6") (pintype "passive"))
      (node (ref "U2") (pin "37") (pinfunction "PC6/TIM3_CH1/TIM8_CH1/FMPI2C1_SCL/I2S2_MCK/USART6_TX/SDIO_D6/DCMI_D0/EVENTOUT_37") (pintype "bidirectional"))
    )
    (net (code "65") (name "RX_3") (class "Default")
      (node (ref "RX3") (pin "1") (pinfunction "1_1") (pintype "passive"))
      (node (ref "RX3") (pin "2") (pinfunction "2_2") (pintype "passive"))
      (node (ref "SV2") (pin "8") (pinfunction "8_8") (pintype "passive"))
      (node (ref "U2") (pin "29") (pinfunction "PB10/TIM2_CH3/I2C2_SCL/SPI2_SCK/I2S2_CK/SAI1_SCK_A/USART3_TX/OTG_HS_ULPI_D3/EVENTOUT_29") (pintype "bidirectional"))
    )
    (net (code "66") (name "R_SW") (class "Default")
      (node (ref "U$4") (pin "P$7") (pinfunction "P$7_P$7") (pintype "bidirectional"))
      (node (ref "U2") (pin "2") (pinfunction "PC13/EVENTOUT_2") (pintype "bidirectional"))
    )
    (net (code "67") (name "S0") (class "Default")
      (node (ref "U$4") (pin "P$17") (pinfunction "P$17_P$17") (pintype "bidirectional"))
      (node (ref "U2") (pin "10") (pinfunction "PC2/SPI2_MISO/OTG_HS_ULPI_DIR/FMC_SDNE0/EVENTOUT_10") (pintype "bidirectional"))
    )
    (net (code "68") (name "S1") (class "Default")
      (node (ref "U$4") (pin "P$18") (pinfunction "P$18_P$18") (pintype "bidirectional"))
      (node (ref "U2") (pin "11") (pinfunction "PC3/SPI2_MOSI/I2S2_SD/OTG_HS_ULPI_NXT/FMC_SDCKE0/EVENTOUT_11") (pintype "bidirectional"))
    )
    (net (code "69") (name "S2") (class "Default")
      (node (ref "U$4") (pin "P$19") (pinfunction "P$19_P$19") (pintype "bidirectional"))
      (node (ref "U2") (pin "24") (pinfunction "PC4/I2S1_MCK/SPDIFRX_IN2/FMC_SDNE0/EVENTOUT_24") (pintype "bidirectional"))
    )
    (net (code "70") (name "S3") (class "Default")
      (node (ref "U$4") (pin "P$20") (pinfunction "P$20_P$20") (pintype "bidirectional"))
      (node (ref "U2") (pin "39") (pinfunction "PC8/TRACED0/TIM3_CH3/TIM8_CH3/UART5_RTS/USART6_CK/SDIO_D0/DCMI_D2/EVENTOUT_39") (pintype "bidirectional"))
    )
    (net (code "71") (name "SCK") (class "Default")
      (node (ref "U$4") (pin "P$11") (pinfunction "P$11_P$11") (pintype "bidirectional"))
      (node (ref "U2") (pin "21") (pinfunction "PA5/TIM2_CH1/TIM2_ETR/TIM8_CH1N/SPI1_SCK/I2S1_CK/OTG_HS_ULPI_CK/EVENTOUT_21") (pintype "bidirectional"))
    )
    (net (code "72") (name "SCL") (class "Default")
      (node (ref "U$3") (pin "P$3") (pinfunction "SCL_P$3") (pintype "bidirectional"))
      (node (ref "U2") (pin "58") (pinfunction "PB6/TIM4_CH1/HDMI_CEC/I2C1_SCL/USART1_TX/CAN2_TX/QUADSPI_BK1_NCS/FMC_SDNE1/DCMI_D5/EVENTOUT_58") (pintype "bidirectional"))
    )
    (net (code "73") (name "SDA") (class "Default")
      (node (ref "U$3") (pin "P$4") (pinfunction "SDA_P$4") (pintype "bidirectional"))
      (node (ref "U2") (pin "59") (pinfunction "PB7/TIM4_CH2/I2C1_SDA/USART1_RX/SPDIFRX_IN0/FMC_NL/DCMI_VSYNC/EVENTOUT_59") (pintype "bidirectional"))
    )
    (net (code "74") (name "ST") (class "Default")
      (node (ref "U$4") (pin "P$6") (pinfunction "P$6_P$6") (pintype "bidirectional"))
      (node (ref "U$5") (pin "P$1") (pinfunction "P$1_P$1") (pintype "bidirectional"))
      (node (ref "U$8") (pin "P$2") (pinfunction "P$2_P$2") (pintype "bidirectional"))
      (node (ref "U$8") (pin "P$5") (pinfunction "P$5_P$5") (pintype "bidirectional"))
      (node (ref "U$9") (pin "P$1") (pinfunction "P$1_P$1") (pintype "bidirectional"))
      (node (ref "U2") (pin "8") (pinfunction "PC0/SAI1_MCLK_B/OTG_HS_ULPI_STP/FMC_SDNWE/EVENTOUT_8") (pintype "bidirectional"))
    )
    (net (code "75") (name "SWO") (class "Default")
      (node (ref "SV1") (pin "6") (pinfunction "6_6") (pintype "passive"))
      (node (ref "U2") (pin "55") (pinfunction "PB3(JTDO/TRACESWO)/JTDO/TRACESWO/TIM2_CH2/I2C2_SDA/SPI1_SCK/I2S1_CK/SPI3_SCK/I2S3_CK/EVENTOUT_55") (pintype "bidirectional"))
    )
    (net (code "76") (name "S_SW") (class "Default")
      (node (ref "U$4") (pin "P$8") (pinfunction "P$8_P$8") (pintype "bidirectional"))
      (node (ref "U2") (pin "3") (pinfunction "PC14-OSC32_IN(PC14)/EVENTOUT_3") (pintype "bidirectional"))
    )
    (net (code "77") (name "TCK") (class "Default")
      (node (ref "SV1") (pin "2") (pinfunction "2_2") (pintype "passive"))
      (node (ref "U2") (pin "49") (pinfunction "PA14/JTCK-SWCLK/EVENTOUT_49") (pintype "bidirectional"))
    )
    (net (code "78") (name "TMS") (class "Default")
      (node (ref "SV1") (pin "4") (pinfunction "4_4") (pintype "passive"))
      (node (ref "U2") (pin "46") (pinfunction "PA13/JTMS-SWDIO/EVENTOUT_46") (pintype "bidirectional"))
    )
    (net (code "79") (name "TX_1") (class "Default")
      (node (ref "SV2") (pin "3") (pinfunction "3_3") (pintype "passive"))
      (node (ref "TX1") (pin "1") (pinfunction "1_1") (pintype "passive"))
      (node (ref "TX1") (pin "2") (pinfunction "2_2") (pintype "passive"))
      (node (ref "U2") (pin "43") (pinfunction "PA10/TIM1_CH3/USART1_RX/OTG_FS_ID/DCMI_D1/EVENTOUT_43") (pintype "bidirectional"))
    )
    (net (code "80") (name "TX_2") (class "Default")
      (node (ref "SV2") (pin "5") (pinfunction "5_5") (pintype "passive"))
      (node (ref "TX2") (pin "1") (pinfunction "1_1") (pintype "passive"))
      (node (ref "TX2") (pin "2") (pinfunction "2_2") (pintype "passive"))
      (node (ref "U2") (pin "38") (pinfunction "PC7/TIM3_CH2/TIM8_CH2/FMPI2C1_SDA/SPI2_SCK/I2S2_CK/I2S3_MCK/SPDIFRX_IN1/USART6_RX/SDIO_D7/DCMI_D1/EVENTOUT_38") (pintype "bidirectional"))
    )
    (net (code "81") (name "TX_3") (class "Default")
      (node (ref "SV2") (pin "7") (pinfunction "7_7") (pintype "passive"))
      (node (ref "TX3") (pin "1") (pinfunction "1_1") (pintype "passive"))
      (node (ref "TX3") (pin "2") (pinfunction "2_2") (pintype "passive"))
      (node (ref "U2") (pin "25") (pinfunction "PC5/USART3_RX/SPDIFRX_IN3/FMC_SDCKE0/EVENTOUT_25") (pintype "bidirectional"))
    )
    (net (code "82") (name "unconnected-(U$1-BOOT-PadP$15)") (class "Default")
      (node (ref "U$1") (pin "P$15") (pinfunction "BOOT_P$15") (pintype "bidirectional"))
    )
    (net (code "83") (name "unconnected-(U$1-FC-PadP$14)") (class "Default")
      (node (ref "U$1") (pin "P$14") (pinfunction "FC_P$14") (pintype "bidirectional"))
    )
    (net (code "84") (name "unconnected-(U$1-P2-PadP$6)") (class "Default")
      (node (ref "U$1") (pin "P$6") (pinfunction "P2_P$6") (pintype "bidirectional"))
    )
    (net (code "85") (name "unconnected-(U$1-P3-PadP$5)") (class "Default")
      (node (ref "U$1") (pin "P$5") (pinfunction "P3_P$5") (pintype "bidirectional"))
    )
    (net (code "86") (name "unconnected-(U$1-P4-PadP$4)") (class "Default")
      (node (ref "U$1") (pin "P$4") (pinfunction "P4_P$4") (pintype "bidirectional"))
    )
    (net (code "87") (name "unconnected-(U$1-VIN-PadP$10)") (class "Default")
      (node (ref "U$1") (pin "P$10") (pinfunction "VIN_P$10") (pintype "bidirectional"))
    )
    (net (code "88") (name "unconnected-(U$3-ADO-PadP$7)") (class "Default")
      (node (ref "U$3") (pin "P$7") (pinfunction "ADO_P$7") (pintype "bidirectional"))
    )
    (net (code "89") (name "unconnected-(U$3-INT-PadP$8)") (class "Default")
      (node (ref "U$3") (pin "P$8") (pinfunction "INT_P$8") (pintype "bidirectional"))
    )
    (net (code "90") (name "unconnected-(U$3-XCL-PadP$6)") (class "Default")
      (node (ref "U$3") (pin "P$6") (pinfunction "XCL_P$6") (pintype "bidirectional"))
    )
    (net (code "91") (name "unconnected-(U$3-XDA-PadP$5)") (class "Default")
      (node (ref "U$3") (pin "P$5") (pinfunction "XDA_P$5") (pintype "bidirectional"))
    )
    (net (code "92") (name "unconnected-(U$8-PadP$3)") (class "Default")
      (node (ref "U$8") (pin "P$3") (pinfunction "P$3_P$3") (pintype "bidirectional"))
    )
    (net (code "93") (name "unconnected-(U$8-PadP$6)") (class "Default")
      (node (ref "U$8") (pin "P$6") (pinfunction "P$6_P$6") (pintype "bidirectional"))
    )
    (net (code "94") (name "unconnected-(U$10-P$3-PadP$2)") (class "Default")
      (node (ref "U$10") (pin "P$2") (pinfunction "P$3_P$2") (pintype "bidirectional"))
    )
  )
)
